# IoTSensorBoardREV2.net
KiCad netlist of a schematic drawn in EAGLE
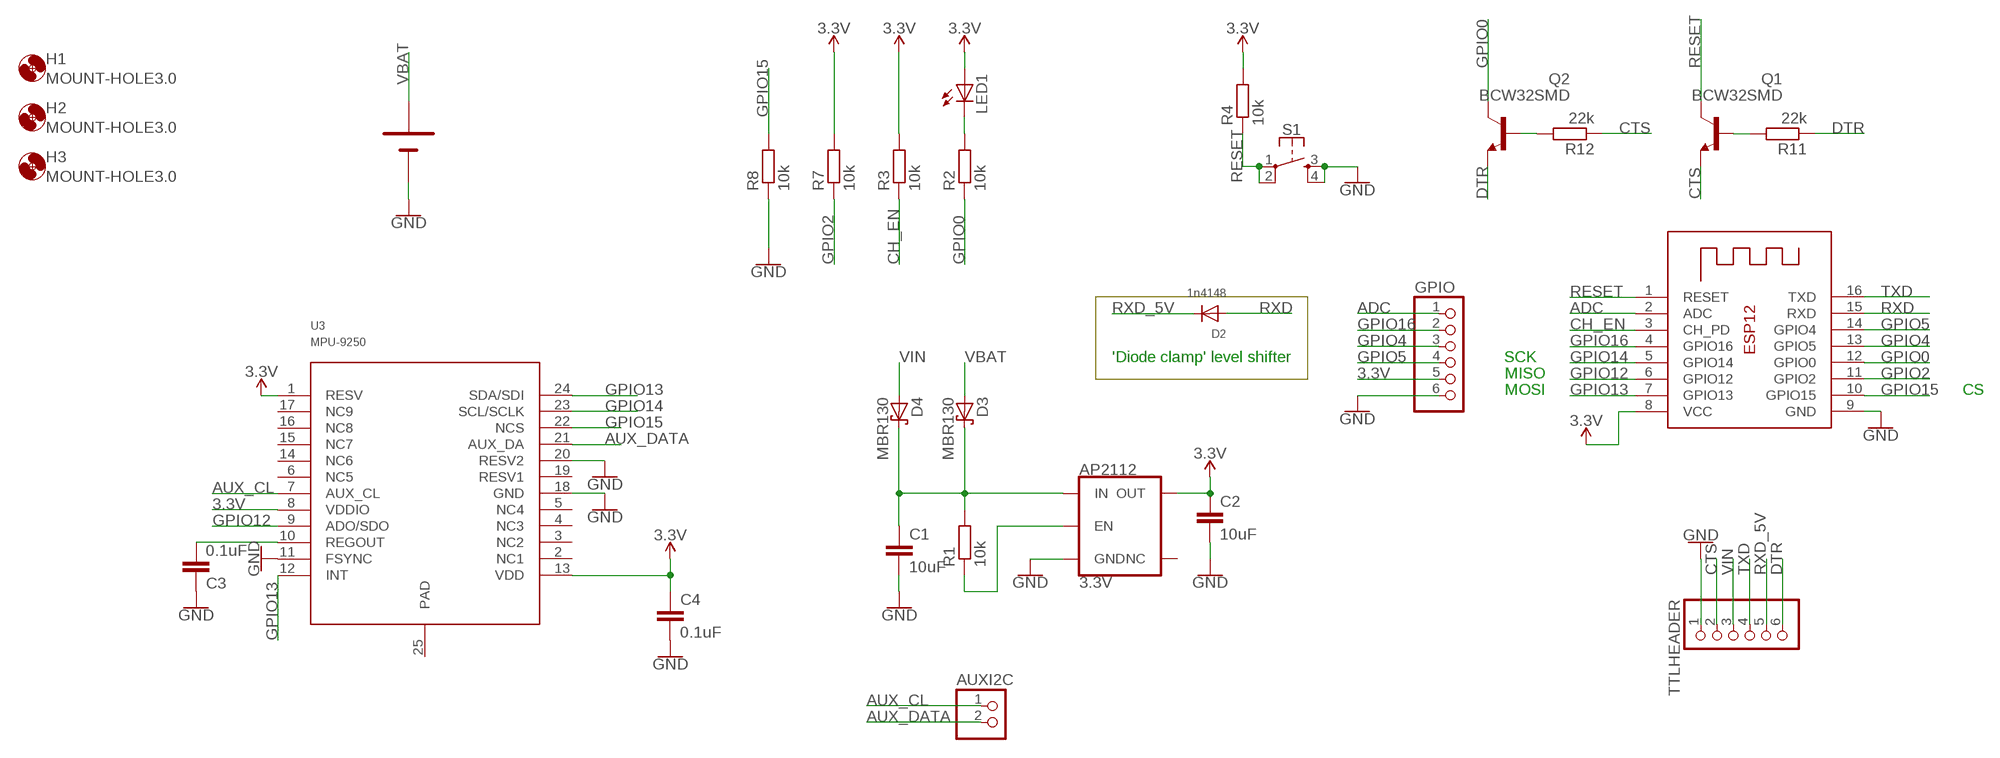
[diagram p0: schematic, sheet 1]

(export (version "E")
  (design (tool "Eeschema 10.0.6"))
  (components
    (comp (ref "AP2112")
      (value "3.3V")
      (footprint "eagle-import:SOT23-5")
      (libsource (lib "eagle-import") (part "V_REG_AP2112K-3.3V"))
    )
    (comp (ref "AUXI2C")
      (value "PINHD-1X2")
      (footprint "eagle-import:1X02")
      (libsource (lib "eagle-import") (part "PINHD-1X2"))
    )
    (comp (ref "C1")
      (value "10uF")
      (footprint "eagle-import:C0805")
      (libsource (lib "eagle-import") (part "C-EUC0805"))
    )
    (comp (ref "C2")
      (value "10uF")
      (footprint "eagle-import:C0805")
      (libsource (lib "eagle-import") (part "C-EUC0805"))
    )
    (comp (ref "C3")
      (value "0.1uF")
      (footprint "eagle-import:C0805")
      (libsource (lib "eagle-import") (part "C-EUC0805"))
    )
    (comp (ref "C4")
      (value "0.1uF")
      (footprint "eagle-import:C0805")
      (libsource (lib "eagle-import") (part "C-EUC0805"))
    )
    (comp (ref "D2")
      (value "1n4148")
      (footprint "eagle-import:SMADIODE")
      (libsource (lib "eagle-import") (part "DIODESMA"))
    )
    (comp (ref "D3")
      (value "MBR130")
      (footprint "eagle-import:SMB")
      (libsource (lib "eagle-import") (part "MBRS130LT3"))
    )
    (comp (ref "D4")
      (value "MBR130")
      (footprint "eagle-import:SMB")
      (libsource (lib "eagle-import") (part "MBRS130LT3"))
    )
    (comp (ref "ESP-12")
      (value "ESP-12")
      (footprint "eagle-import:ESP-12")
      (libsource (lib "eagle-import") (part "ESP-12"))
    )
    (comp (ref "GPIO")
      (value "PINHD-1X6")
      (footprint "eagle-import:1X06")
      (libsource (lib "eagle-import") (part "PINHD-1X6"))
    )
    (comp (ref "H1")
      (value "MOUNT-HOLE3.0")
      (footprint "eagle-import:3,0")
      (libsource (lib "eagle-import") (part "MOUNT-HOLE3.0"))
    )
    (comp (ref "H2")
      (value "MOUNT-HOLE3.0")
      (footprint "eagle-import:3,0")
      (libsource (lib "eagle-import") (part "MOUNT-HOLE3.0"))
    )
    (comp (ref "H3")
      (value "MOUNT-HOLE3.0")
      (footprint "eagle-import:3,0")
      (libsource (lib "eagle-import") (part "MOUNT-HOLE3.0"))
    )
    (comp (ref "LED1")
      (value "LEDCHIP-LED0805")
      (footprint "eagle-import:CHIP-LED0805")
      (libsource (lib "eagle-import") (part "LEDCHIP-LED0805"))
    )
    (comp (ref "Q1")
      (value "BCW32SMD")
      (footprint "eagle-import:SOT23-BEC")
      (libsource (lib "eagle-import") (part "BCW32SMD"))
    )
    (comp (ref "Q2")
      (value "BCW32SMD")
      (footprint "eagle-import:SOT23-BEC")
      (libsource (lib "eagle-import") (part "BCW32SMD"))
    )
    (comp (ref "R1")
      (value "10k")
      (footprint "eagle-import:R0805")
      (libsource (lib "eagle-import") (part "R-EU_R0805"))
    )
    (comp (ref "R2")
      (value "10k")
      (footprint "eagle-import:R0805")
      (libsource (lib "eagle-import") (part "R-EU_R0805"))
    )
    (comp (ref "R3")
      (value "10k")
      (footprint "eagle-import:R0805")
      (libsource (lib "eagle-import") (part "R-EU_R0805"))
    )
    (comp (ref "R4")
      (value "10k")
      (footprint "eagle-import:R0805")
      (libsource (lib "eagle-import") (part "R-EU_R0805"))
    )
    (comp (ref "R7")
      (value "10k")
      (footprint "eagle-import:R0805")
      (libsource (lib "eagle-import") (part "R-EU_R0805"))
    )
    (comp (ref "R8")
      (value "10k")
      (footprint "eagle-import:R0805")
      (libsource (lib "eagle-import") (part "R-EU_R0805"))
    )
    (comp (ref "R11")
      (value "22k")
      (footprint "eagle-import:R0805")
      (libsource (lib "eagle-import") (part "R-EU_R0805"))
    )
    (comp (ref "R12")
      (value "22k")
      (footprint "eagle-import:R0805")
      (libsource (lib "eagle-import") (part "R-EU_R0805"))
    )
    (comp (ref "S1")
      (value "MOMENTARY-SWITCH-SPST-2-SMD-5.2MM")
      (footprint "eagle-import:TACTILE_SWITCH_SMD_5.2MM")
      (libsource (lib "eagle-import") (part "MOMENTARY-SWITCH-SPST-2-SMD-5.2MM"))
    )
    (comp (ref "TTLHEADER")
      (value "PINHD-1X6")
      (footprint "eagle-import:1X06")
      (libsource (lib "eagle-import") (part "PINHD-1X6"))
    )
    (comp (ref "U$1")
      (value "SMTU_2450N")
      (footprint "eagle-import:SMTU_2450N")
      (libsource (lib "eagle-import") (part "SMTU_2450N"))
    )
    (comp (ref "U3")
      (value "MPU-9250")
      (footprint "eagle-import:LEAD-QFN24")
      (libsource (lib "eagle-import") (part "MPU-9250"))
    )
  )
  (nets
    (net (code "1") (name "/ADC") (class "Default")
      (node (ref "ESP-12") (pin "2") (pinfunction "ADC_2") (pintype "passive"))
      (node (ref "GPIO") (pin "1") (pinfunction "1_1") (pintype "passive"))
    )
    (net (code "2") (name "/AUX_CL") (class "Default")
      (node (ref "AUXI2C") (pin "1") (pinfunction "1_1") (pintype "passive"))
      (node (ref "U3") (pin "7") (pinfunction "AUX_CL_7") (pintype "bidirectional"))
    )
    (net (code "3") (name "/AUX_DATA") (class "Default")
      (node (ref "AUXI2C") (pin "2") (pinfunction "2_2") (pintype "passive"))
      (node (ref "U3") (pin "21") (pinfunction "AUX_DA_21") (pintype "bidirectional"))
    )
    (net (code "4") (name "/CH_EN") (class "Default")
      (node (ref "ESP-12") (pin "3") (pinfunction "CH_PD_3") (pintype "input"))
      (node (ref "R3") (pin "1") (pinfunction "1_1") (pintype "passive"))
    )
    (net (code "5") (name "/CTS") (class "Default")
      (node (ref "Q1") (pin "E") (pinfunction "E_E") (pintype "passive"))
      (node (ref "R12") (pin "1") (pinfunction "1_1") (pintype "passive"))
      (node (ref "TTLHEADER") (pin "2") (pinfunction "2_2") (pintype "passive"))
    )
    (net (code "6") (name "/DTR") (class "Default")
      (node (ref "Q2") (pin "E") (pinfunction "E_E") (pintype "passive"))
      (node (ref "R11") (pin "1") (pinfunction "1_1") (pintype "passive"))
      (node (ref "TTLHEADER") (pin "6") (pinfunction "6_6") (pintype "passive"))
    )
    (net (code "7") (name "/GPIO0") (class "Default")
      (node (ref "ESP-12") (pin "12") (pinfunction "GPIO0_12") (pintype "bidirectional"))
      (node (ref "Q2") (pin "C") (pinfunction "C_C") (pintype "passive"))
      (node (ref "R2") (pin "1") (pinfunction "1_1") (pintype "passive"))
    )
    (net (code "8") (name "/GPIO2") (class "Default")
      (node (ref "ESP-12") (pin "11") (pinfunction "GPIO2_11") (pintype "bidirectional"))
      (node (ref "R7") (pin "1") (pinfunction "1_1") (pintype "passive"))
    )
    (net (code "9") (name "/GPIO4") (class "Default")
      (node (ref "ESP-12") (pin "13") (pinfunction "GPIO5_13") (pintype "bidirectional"))
      (node (ref "GPIO") (pin "3") (pinfunction "3_3") (pintype "passive"))
    )
    (net (code "10") (name "/GPIO5") (class "Default")
      (node (ref "ESP-12") (pin "14") (pinfunction "GPIO4_14") (pintype "bidirectional"))
      (node (ref "GPIO") (pin "4") (pinfunction "4_4") (pintype "passive"))
    )
    (net (code "11") (name "/GPIO12") (class "Default")
      (node (ref "ESP-12") (pin "6") (pinfunction "GPIO12_6") (pintype "bidirectional"))
      (node (ref "U3") (pin "9") (pinfunction "ADO/SDO_9") (pintype "bidirectional"))
    )
    (net (code "12") (name "/GPIO13") (class "Default")
      (node (ref "ESP-12") (pin "7") (pinfunction "GPIO13_7") (pintype "bidirectional"))
      (node (ref "U3") (pin "12") (pinfunction "INT_12") (pintype "bidirectional"))
      (node (ref "U3") (pin "24") (pinfunction "SDA/SDI_24") (pintype "bidirectional"))
    )
    (net (code "13") (name "/GPIO14") (class "Default")
      (node (ref "ESP-12") (pin "5") (pinfunction "GPIO14_5") (pintype "bidirectional"))
      (node (ref "U3") (pin "23") (pinfunction "SCL/SCLK_23") (pintype "bidirectional"))
    )
    (net (code "14") (name "/GPIO15") (class "Default")
      (node (ref "ESP-12") (pin "10") (pinfunction "GPIO15_10") (pintype "bidirectional"))
      (node (ref "R8") (pin "2") (pinfunction "2_2") (pintype "passive"))
      (node (ref "U3") (pin "22") (pinfunction "NCS_22") (pintype "bidirectional"))
    )
    (net (code "15") (name "/GPIO16") (class "Default")
      (node (ref "ESP-12") (pin "4") (pinfunction "GPIO16_4") (pintype "bidirectional"))
      (node (ref "GPIO") (pin "2") (pinfunction "2_2") (pintype "passive"))
    )
    (net (code "16") (name "/RESET") (class "Default")
      (node (ref "ESP-12") (pin "1") (pinfunction "RESET_1") (pintype "input"))
      (node (ref "Q1") (pin "C") (pinfunction "C_C") (pintype "passive"))
      (node (ref "R4") (pin "1") (pinfunction "1_1") (pintype "passive"))
      (node (ref "S1") (pin "1") (pinfunction "1_1") (pintype "passive"))
      (node (ref "S1") (pin "2") (pinfunction "2_2") (pintype "passive"))
    )
    (net (code "17") (name "/RXD") (class "Default")
      (node (ref "D2") (pin "A") (pinfunction "A_A") (pintype "passive"))
      (node (ref "ESP-12") (pin "15") (pinfunction "RXD_15") (pintype "input"))
    )
    (net (code "18") (name "/RXD_5V") (class "Default")
      (node (ref "D2") (pin "C") (pinfunction "C_C") (pintype "passive"))
      (node (ref "TTLHEADER") (pin "5") (pinfunction "5_5") (pintype "passive"))
    )
    (net (code "19") (name "/TXD") (class "Default")
      (node (ref "ESP-12") (pin "16") (pinfunction "TXD_16") (pintype "output"))
      (node (ref "TTLHEADER") (pin "4") (pinfunction "4_4") (pintype "passive"))
    )
    (net (code "20") (name "/VBAT") (class "Default")
      (node (ref "D3") (pin "A") (pinfunction "A_A") (pintype "passive"))
      (node (ref "U$1") (pin "P$2") (pinfunction "P$2P_P$2") (pintype "bidirectional"))
    )
    (net (code "21") (name "/VIN") (class "Default")
      (node (ref "D4") (pin "A") (pinfunction "A_A") (pintype "passive"))
      (node (ref "TTLHEADER") (pin "3") (pinfunction "3_3") (pintype "passive"))
    )
    (net (code "22") (name "3.3V") (class "Default")
      (node (ref "AP2112") (pin "5") (pinfunction "OUT_5") (pintype "passive"))
      (node (ref "C2") (pin "1") (pinfunction "1_1") (pintype "passive"))
      (node (ref "C4") (pin "1") (pinfunction "1_1") (pintype "passive"))
      (node (ref "ESP-12") (pin "8") (pinfunction "VCC_8") (pintype "power_in"))
      (node (ref "GPIO") (pin "5") (pinfunction "5_5") (pintype "passive"))
      (node (ref "LED1") (pin "A") (pinfunction "A_A") (pintype "passive"))
      (node (ref "R3") (pin "2") (pinfunction "2_2") (pintype "passive"))
      (node (ref "R4") (pin "2") (pinfunction "2_2") (pintype "passive"))
      (node (ref "R7") (pin "2") (pinfunction "2_2") (pintype "passive"))
      (node (ref "U3") (pin "1") (pinfunction "RESV_1") (pintype "bidirectional"))
      (node (ref "U3") (pin "13") (pinfunction "VDD_13") (pintype "bidirectional"))
      (node (ref "U3") (pin "8") (pinfunction "VDDIO_8") (pintype "bidirectional"))
    )
    (net (code "23") (name "GND") (class "Default")
      (node (ref "AP2112") (pin "2") (pinfunction "GND_2") (pintype "input"))
      (node (ref "C1") (pin "2") (pinfunction "2_2") (pintype "passive"))
      (node (ref "C2") (pin "2") (pinfunction "2_2") (pintype "passive"))
      (node (ref "C3") (pin "1") (pinfunction "1_1") (pintype "passive"))
      (node (ref "C4") (pin "2") (pinfunction "2_2") (pintype "passive"))
      (node (ref "ESP-12") (pin "9") (pinfunction "GND_9") (pintype "power_in"))
      (node (ref "GPIO") (pin "6") (pinfunction "6_6") (pintype "passive"))
      (node (ref "R8") (pin "1") (pinfunction "1_1") (pintype "passive"))
      (node (ref "S1") (pin "3") (pinfunction "3_3") (pintype "passive"))
      (node (ref "S1") (pin "4") (pinfunction "4_4") (pintype "passive"))
      (node (ref "TTLHEADER") (pin "1") (pinfunction "1_1") (pintype "passive"))
      (node (ref "U$1") (pin "P$1") (pinfunction "P$1N_P$1") (pintype "bidirectional"))
      (node (ref "U3") (pin "11") (pinfunction "FSYNC_11") (pintype "bidirectional"))
      (node (ref "U3") (pin "18") (pinfunction "GND_18") (pintype "bidirectional"))
      (node (ref "U3") (pin "20") (pinfunction "RESV2_20") (pintype "bidirectional"))
    )
    (net (code "24") (name "Net-(AP2112-EN)") (class "Default")
      (node (ref "AP2112") (pin "3") (pinfunction "EN_3") (pintype "input"))
      (node (ref "R1") (pin "1") (pinfunction "1_1") (pintype "passive"))
    )
    (net (code "25") (name "Net-(AP2112-IN)") (class "Default")
      (node (ref "AP2112") (pin "1") (pinfunction "IN_1") (pintype "input"))
      (node (ref "C1") (pin "1") (pinfunction "1_1") (pintype "passive"))
      (node (ref "D3") (pin "C") (pinfunction "C_C") (pintype "passive"))
      (node (ref "D4") (pin "C") (pinfunction "C_C") (pintype "passive"))
      (node (ref "R1") (pin "2") (pinfunction "2_2") (pintype "passive"))
    )
    (net (code "26") (name "Net-(LED1-PadC)") (class "Default")
      (node (ref "LED1") (pin "C") (pinfunction "C_C") (pintype "passive"))
      (node (ref "R2") (pin "2") (pinfunction "2_2") (pintype "passive"))
    )
    (net (code "27") (name "Net-(Q1-PadB)") (class "Default")
      (node (ref "Q1") (pin "B") (pinfunction "B_B") (pintype "passive"))
      (node (ref "R11") (pin "2") (pinfunction "2_2") (pintype "passive"))
    )
    (net (code "28") (name "Net-(Q2-PadB)") (class "Default")
      (node (ref "Q2") (pin "B") (pinfunction "B_B") (pintype "passive"))
      (node (ref "R12") (pin "2") (pinfunction "2_2") (pintype "passive"))
    )
    (net (code "29") (name "Net-(U3-REGOUT)") (class "Default")
      (node (ref "C3") (pin "2") (pinfunction "2_2") (pintype "passive"))
      (node (ref "U3") (pin "10") (pinfunction "REGOUT_10") (pintype "bidirectional"))
    )
    (net (code "30") (name "unconnected-(AP2112-NC-Pad4)") (class "Default")
      (node (ref "AP2112") (pin "4") (pinfunction "NC_4") (pintype "no_connect"))
    )
    (net (code "31") (name "unconnected-(U3-NC1-Pad2)") (class "Default")
      (node (ref "U3") (pin "2") (pinfunction "NC1_2") (pintype "bidirectional"))
    )
    (net (code "32") (name "unconnected-(U3-NC2-Pad3)") (class "Default")
      (node (ref "U3") (pin "3") (pinfunction "NC2_3") (pintype "bidirectional"))
    )
    (net (code "33") (name "unconnected-(U3-NC3-Pad4)") (class "Default")
      (node (ref "U3") (pin "4") (pinfunction "NC3_4") (pintype "bidirectional"))
    )
    (net (code "34") (name "unconnected-(U3-NC4-Pad5)") (class "Default")
      (node (ref "U3") (pin "5") (pinfunction "NC4_5") (pintype "bidirectional"))
    )
    (net (code "35") (name "unconnected-(U3-NC5-Pad6)") (class "Default")
      (node (ref "U3") (pin "6") (pinfunction "NC5_6") (pintype "bidirectional"))
    )
    (net (code "36") (name "unconnected-(U3-NC6-Pad14)") (class "Default")
      (node (ref "U3") (pin "14") (pinfunction "NC6_14") (pintype "bidirectional"))
    )
    (net (code "37") (name "unconnected-(U3-NC7-Pad15)") (class "Default")
      (node (ref "U3") (pin "15") (pinfunction "NC7_15") (pintype "bidirectional"))
    )
    (net (code "38") (name "unconnected-(U3-NC8-Pad16)") (class "Default")
      (node (ref "U3") (pin "16") (pinfunction "NC8_16") (pintype "bidirectional"))
    )
    (net (code "39") (name "unconnected-(U3-NC9-Pad17)") (class "Default")
      (node (ref "U3") (pin "17") (pinfunction "NC9_17") (pintype "bidirectional"))
    )
    (net (code "40") (name "unconnected-(U3-PAD-Pad25)") (class "Default")
      (node (ref "U3") (pin "25") (pinfunction "PAD_25") (pintype "bidirectional"))
    )
    (net (code "41") (name "unconnected-(U3-RESV1-Pad19)") (class "Default")
      (node (ref "U3") (pin "19") (pinfunction "RESV1_19") (pintype "bidirectional"))
    )
  )
)
